# 07_CONFIG.net
KiCad netlist of a schematic drawn in Altium Designer
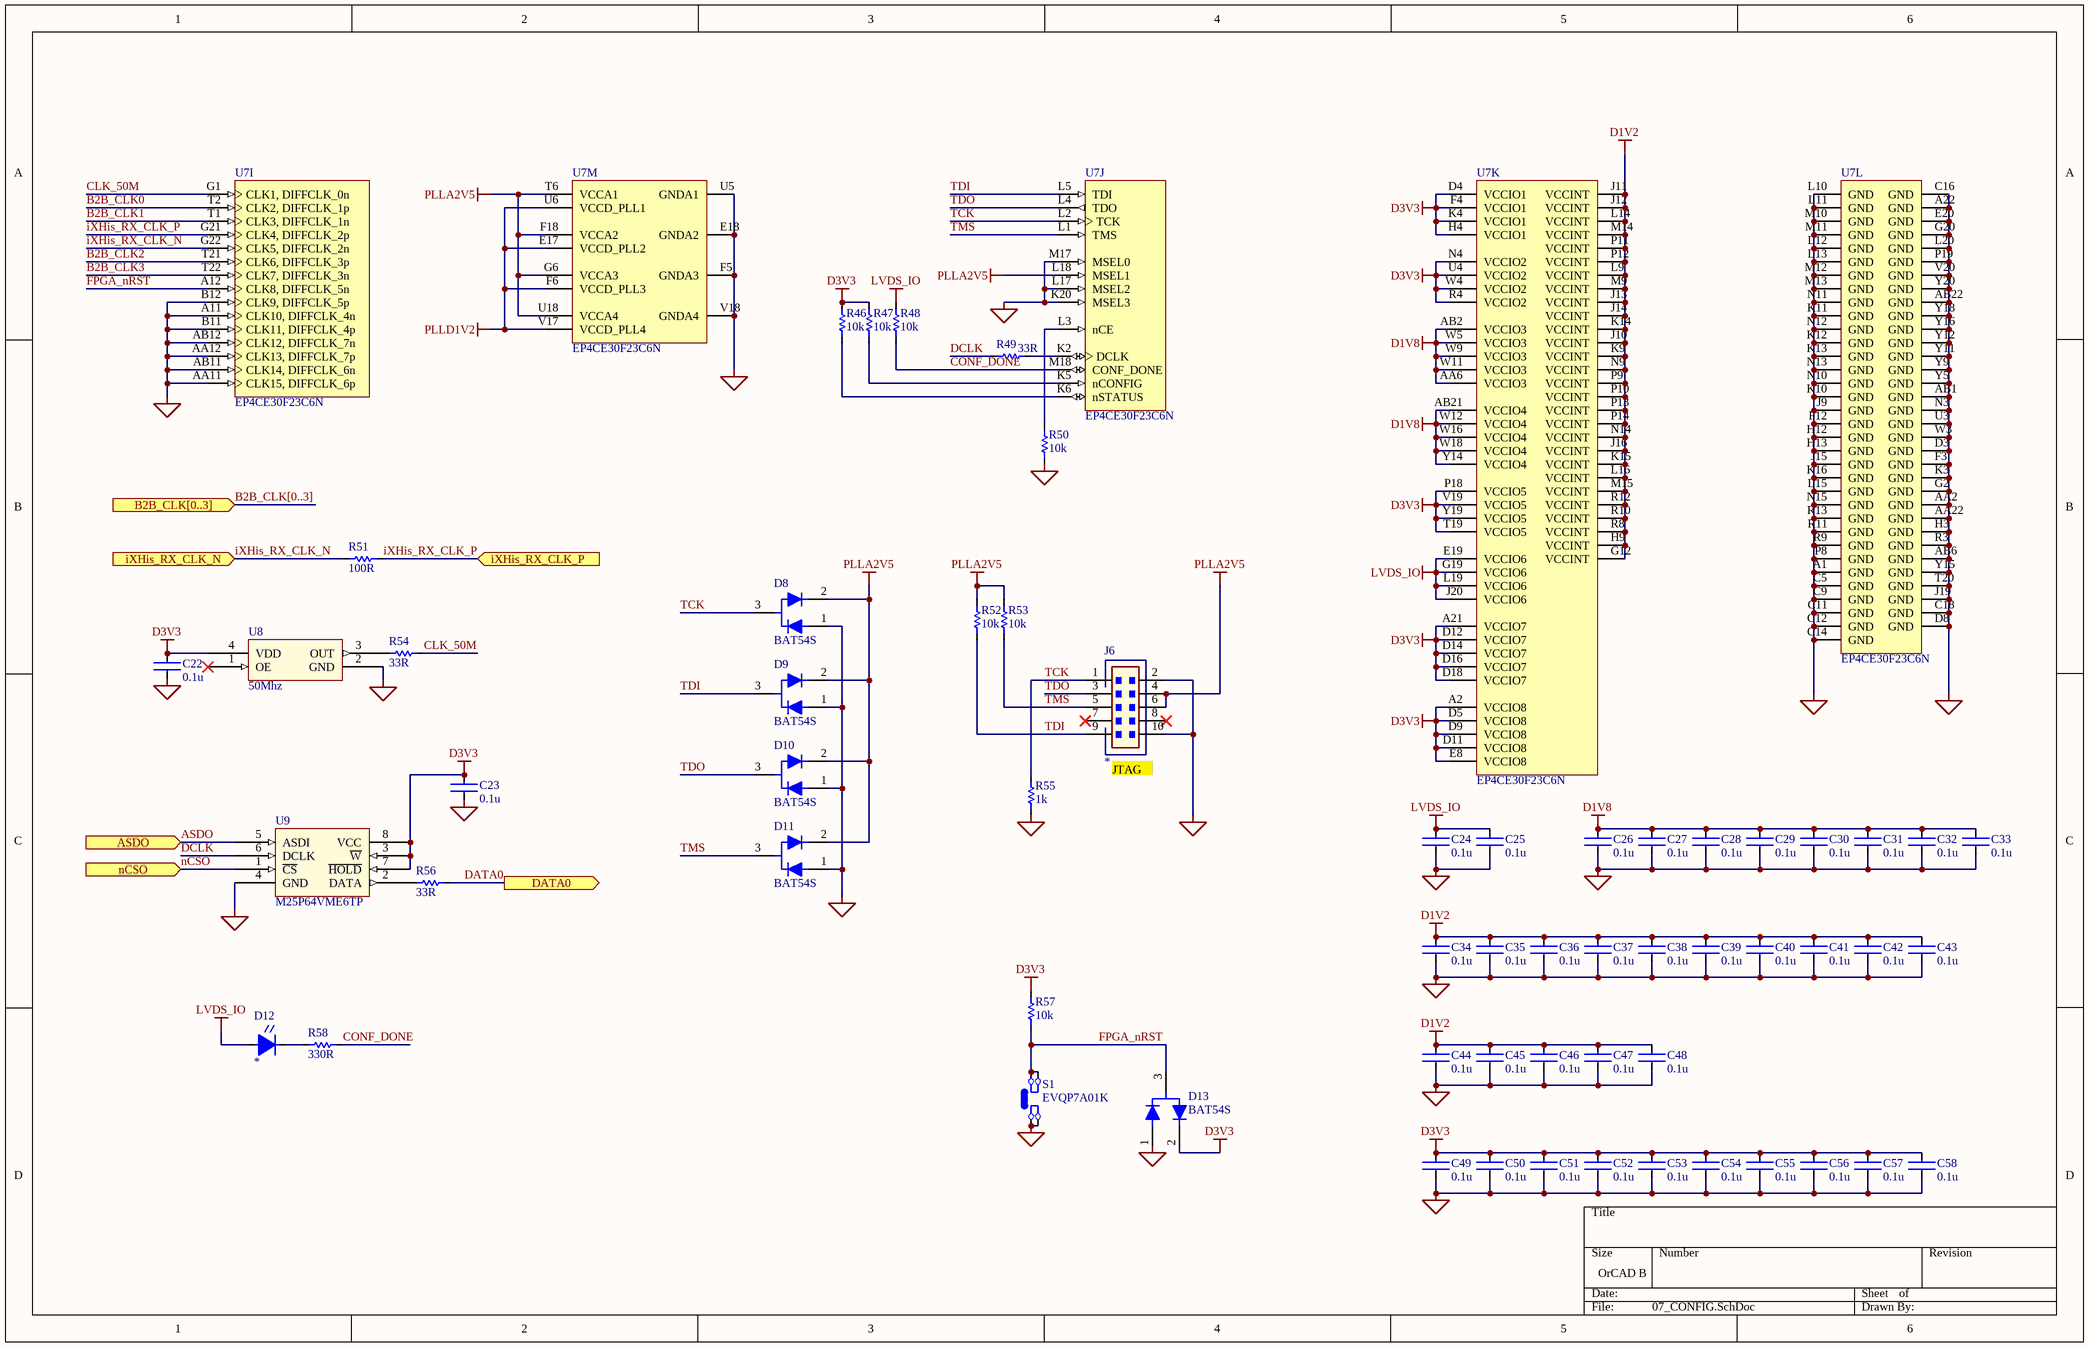
[diagram p0: 07_CONFIG.SchDoc]

(export (version "E")
  (design (tool "Eeschema 10.0.6"))
  (components
    (comp (ref "C22")
      (value "0.1u")
      (footprint "C0402")
      (description "CAP,Ceramic,X7R,10%,16V,0.1uF,0402")
      (libsource (lib "C0402") (part "CAP011"))
    )
    (comp (ref "C23")
      (value "0.1u")
      (footprint "C0402")
      (description "CAP,Ceramic,X7R,10%,16V,0.1uF,0402")
      (libsource (lib "C0402") (part "CAP011"))
    )
    (comp (ref "C24")
      (value "0.1u")
      (footprint "C0402")
      (description "CAP,Ceramic,X7R,10%,16V,0.1uF,0402")
      (libsource (lib "C0402") (part "CAP011"))
    )
    (comp (ref "C25")
      (value "0.1u")
      (footprint "C0402")
      (description "CAP,Ceramic,X7R,10%,16V,0.1uF,0402")
      (libsource (lib "C0402") (part "CAP011"))
    )
    (comp (ref "C26")
      (value "0.1u")
      (footprint "C0402")
      (description "CAP,Ceramic,X7R,10%,16V,0.1uF,0402")
      (libsource (lib "C0402") (part "CAP011"))
    )
    (comp (ref "C27")
      (value "0.1u")
      (footprint "C0402")
      (description "CAP,Ceramic,X7R,10%,16V,0.1uF,0402")
      (libsource (lib "C0402") (part "CAP011"))
    )
    (comp (ref "C28")
      (value "0.1u")
      (footprint "C0402")
      (description "CAP,Ceramic,X7R,10%,16V,0.1uF,0402")
      (libsource (lib "C0402") (part "CAP011"))
    )
    (comp (ref "C29")
      (value "0.1u")
      (footprint "C0402")
      (description "CAP,Ceramic,X7R,10%,16V,0.1uF,0402")
      (libsource (lib "C0402") (part "CAP011"))
    )
    (comp (ref "C30")
      (value "0.1u")
      (footprint "C0402")
      (description "CAP,Ceramic,X7R,10%,16V,0.1uF,0402")
      (libsource (lib "C0402") (part "CAP011"))
    )
    (comp (ref "C31")
      (value "0.1u")
      (footprint "C0402")
      (description "CAP,Ceramic,X7R,10%,16V,0.1uF,0402")
      (libsource (lib "C0402") (part "CAP011"))
    )
    (comp (ref "C32")
      (value "0.1u")
      (footprint "C0402")
      (description "CAP,Ceramic,X7R,10%,16V,0.1uF,0402")
      (libsource (lib "C0402") (part "CAP011"))
    )
    (comp (ref "C33")
      (value "0.1u")
      (footprint "C0402")
      (description "CAP,Ceramic,X7R,10%,16V,0.1uF,0402")
      (libsource (lib "C0402") (part "CAP011"))
    )
    (comp (ref "C34")
      (value "0.1u")
      (footprint "C0402")
      (description "CAP,Ceramic,X7R,10%,16V,0.1uF,0402")
      (libsource (lib "C0402") (part "CAP011"))
    )
    (comp (ref "C35")
      (value "0.1u")
      (footprint "C0402")
      (description "CAP,Ceramic,X7R,10%,16V,0.1uF,0402")
      (libsource (lib "C0402") (part "CAP011"))
    )
    (comp (ref "C36")
      (value "0.1u")
      (footprint "C0402")
      (description "CAP,Ceramic,X7R,10%,16V,0.1uF,0402")
      (libsource (lib "C0402") (part "CAP011"))
    )
    (comp (ref "C37")
      (value "0.1u")
      (footprint "C0402")
      (description "CAP,Ceramic,X7R,10%,16V,0.1uF,0402")
      (libsource (lib "C0402") (part "CAP011"))
    )
    (comp (ref "C38")
      (value "0.1u")
      (footprint "C0402")
      (description "CAP,Ceramic,X7R,10%,16V,0.1uF,0402")
      (libsource (lib "C0402") (part "CAP011"))
    )
    (comp (ref "C39")
      (value "0.1u")
      (footprint "C0402")
      (description "CAP,Ceramic,X7R,10%,16V,0.1uF,0402")
      (libsource (lib "C0402") (part "CAP011"))
    )
    (comp (ref "C40")
      (value "0.1u")
      (footprint "C0402")
      (description "CAP,Ceramic,X7R,10%,16V,0.1uF,0402")
      (libsource (lib "C0402") (part "CAP011"))
    )
    (comp (ref "C41")
      (value "0.1u")
      (footprint "C0402")
      (description "CAP,Ceramic,X7R,10%,16V,0.1uF,0402")
      (libsource (lib "C0402") (part "CAP011"))
    )
    (comp (ref "C42")
      (value "0.1u")
      (footprint "C0402")
      (description "CAP,Ceramic,X7R,10%,16V,0.1uF,0402")
      (libsource (lib "C0402") (part "CAP011"))
    )
    (comp (ref "C43")
      (value "0.1u")
      (footprint "C0402")
      (description "CAP,Ceramic,X7R,10%,16V,0.1uF,0402")
      (libsource (lib "C0402") (part "CAP011"))
    )
    (comp (ref "C44")
      (value "0.1u")
      (footprint "C0402")
      (description "CAP,Ceramic,X7R,10%,16V,0.1uF,0402")
      (libsource (lib "C0402") (part "CAP011"))
    )
    (comp (ref "C45")
      (value "0.1u")
      (footprint "C0402")
      (description "CAP,Ceramic,X7R,10%,16V,0.1uF,0402")
      (libsource (lib "C0402") (part "CAP011"))
    )
    (comp (ref "C46")
      (value "0.1u")
      (footprint "C0402")
      (description "CAP,Ceramic,X7R,10%,16V,0.1uF,0402")
      (libsource (lib "C0402") (part "CAP011"))
    )
    (comp (ref "C47")
      (value "0.1u")
      (footprint "C0402")
      (description "CAP,Ceramic,X7R,10%,16V,0.1uF,0402")
      (libsource (lib "C0402") (part "CAP011"))
    )
    (comp (ref "C48")
      (value "0.1u")
      (footprint "C0402")
      (description "CAP,Ceramic,X7R,10%,16V,0.1uF,0402")
      (libsource (lib "C0402") (part "CAP011"))
    )
    (comp (ref "C49")
      (value "0.1u")
      (footprint "C0402")
      (description "CAP,Ceramic,X7R,10%,16V,0.1uF,0402")
      (libsource (lib "C0402") (part "CAP011"))
    )
    (comp (ref "C50")
      (value "0.1u")
      (footprint "C0402")
      (description "CAP,Ceramic,X7R,10%,16V,0.1uF,0402")
      (libsource (lib "C0402") (part "CAP011"))
    )
    (comp (ref "C51")
      (value "0.1u")
      (footprint "C0402")
      (description "CAP,Ceramic,X7R,10%,16V,0.1uF,0402")
      (libsource (lib "C0402") (part "CAP011"))
    )
    (comp (ref "C52")
      (value "0.1u")
      (footprint "C0402")
      (description "CAP,Ceramic,X7R,10%,16V,0.1uF,0402")
      (libsource (lib "C0402") (part "CAP011"))
    )
    (comp (ref "C53")
      (value "0.1u")
      (footprint "C0402")
      (description "CAP,Ceramic,X7R,10%,16V,0.1uF,0402")
      (libsource (lib "C0402") (part "CAP011"))
    )
    (comp (ref "C54")
      (value "0.1u")
      (footprint "C0402")
      (description "CAP,Ceramic,X7R,10%,16V,0.1uF,0402")
      (libsource (lib "C0402") (part "CAP011"))
    )
    (comp (ref "C55")
      (value "0.1u")
      (footprint "C0402")
      (description "CAP,Ceramic,X7R,10%,16V,0.1uF,0402")
      (libsource (lib "C0402") (part "CAP011"))
    )
    (comp (ref "C56")
      (value "0.1u")
      (footprint "C0402")
      (description "CAP,Ceramic,X7R,10%,16V,0.1uF,0402")
      (libsource (lib "C0402") (part "CAP011"))
    )
    (comp (ref "C57")
      (value "0.1u")
      (footprint "C0402")
      (description "CAP,Ceramic,X7R,10%,16V,0.1uF,0402")
      (libsource (lib "C0402") (part "CAP011"))
    )
    (comp (ref "C58")
      (value "0.1u")
      (footprint "C0402")
      (description "CAP,Ceramic,X7R,10%,16V,0.1uF,0402")
      (libsource (lib "C0402") (part "CAP011"))
    )
    (comp (ref "D8")
      (value "BAT54S")
      (footprint "SOT95P230X110-3N_SOT23_BAT54")
      (description "Schottky Double Diodes,30V,200mA,SOT23,a1k2k1a2")
      (libsource (lib "AD15_schlib") (part "BAT54S"))
    )
    (comp (ref "D9")
      (value "BAT54S")
      (footprint "SOT95P230X110-3N_SOT23_BAT54")
      (description "Schottky Double Diodes,30V,200mA,SOT23,a1k2k1a2")
      (libsource (lib "AD15_schlib") (part "BAT54S"))
    )
    (comp (ref "D10")
      (value "BAT54S")
      (footprint "SOT95P230X110-3N_SOT23_BAT54")
      (description "Schottky Double Diodes,30V,200mA,SOT23,a1k2k1a2")
      (libsource (lib "AD15_schlib") (part "BAT54S"))
    )
    (comp (ref "D11")
      (value "BAT54S")
      (footprint "SOT95P230X110-3N_SOT23_BAT54")
      (description "Schottky Double Diodes,30V,200mA,SOT23,a1k2k1a2")
      (libsource (lib "AD15_schlib") (part "BAT54S"))
    )
    (comp (ref "D12")
      (value "*")
      (footprint "LED0603")
      (description "LED,Yellow Green,2V,20mA,0603")
      (libsource (lib "AD15_schlib") (part "LED YellowGreen0603"))
    )
    (comp (ref "D13")
      (value "BAT54S")
      (footprint "SOT95P230X110-3N_SOT23_BAT54")
      (description "Schottky Double Diodes,30V,200mA,SOT23,a1k2k1a2")
      (libsource (lib "AD15_schlib") (part "BAT54S"))
    )
    (comp (ref "J6")
      (value "JTAG")
      (footprint "3011001XXX00")
      (description "Header,10Pin,Vertical,2.54mm Pitch,TH")
      (fields (field (name "COMMENT_1") "*"))
      (libsource (lib "AD15_schlib") (part "3011001XXX00"))
    )
    (comp (ref "R46")
      (value "10k")
      (footprint "R0402")
      (description "RES,10k,1%,1/16W,0402")
      (libsource (lib "R0402") (part "RES012"))
    )
    (comp (ref "R47")
      (value "10k")
      (footprint "R0402")
      (description "RES,10k,1%,1/16W,0402")
      (libsource (lib "R0402") (part "RES012"))
    )
    (comp (ref "R48")
      (value "10k")
      (footprint "R0402")
      (description "RES,10k,1%,1/16W,0402")
      (libsource (lib "R0402") (part "RES012"))
    )
    (comp (ref "R49")
      (value "33R")
      (footprint "R0402")
      (description "RES,33R,1%,1/16W,0402")
      (libsource (lib "R0402") (part "RES017"))
    )
    (comp (ref "R50")
      (value "10k")
      (footprint "R0402")
      (description "RES,10k,1%,1/16W,0402")
      (libsource (lib "R0402") (part "RES012"))
    )
    (comp (ref "R51")
      (value "100R")
      (footprint "R0402")
      (description "RES,100R,1%,1/16W,0402")
      (libsource (lib "R0402") (part "RES019"))
    )
    (comp (ref "R52")
      (value "10k")
      (footprint "R0402")
      (description "RES,10k,1%,1/16W,0402")
      (libsource (lib "R0402") (part "RES012"))
    )
    (comp (ref "R53")
      (value "10k")
      (footprint "R0402")
      (description "RES,10k,1%,1/16W,0402")
      (libsource (lib "R0402") (part "RES012"))
    )
    (comp (ref "R54")
      (value "33R")
      (footprint "R0402")
      (description "RES,33R,1%,1/16W,0402")
      (libsource (lib "R0402") (part "RES017"))
    )
    (comp (ref "R55")
      (value "1k")
      (footprint "R0402")
      (description "RES,1k,1%,1/16W,0402")
      (libsource (lib "R0402") (part "RES011"))
    )
    (comp (ref "R56")
      (value "33R")
      (footprint "R0402")
      (description "RES,33R,1%,1/16W,0402")
      (libsource (lib "R0402") (part "RES017"))
    )
    (comp (ref "R57")
      (value "10k")
      (footprint "R0402")
      (description "RES,10k,1%,1/16W,0402")
      (libsource (lib "R0402") (part "RES012"))
    )
    (comp (ref "R58")
      (value "330R")
      (footprint "R0402")
      (description "RES,330R,1%,1/16W,0402")
      (libsource (lib "R0402") (part "RES0111"))
    )
    (comp (ref "S1")
      (value "EVQP7A01K")
      (footprint "EVQP7A01K")
      (description "Switch,3.5x2.9,Normal open,SMD")
      (libsource (lib "AD15_schlib") (part "EVQP7A01K"))
    )
    (comp (ref "U7")
      (value "EP4CE30F23C6N")
      (footprint "FBGA484_EP4CE30F23C6N")
      (description "IC,FPGA,28848 LEs,Speed-6,FBGA484")
      (libsource (lib "AD15_Altera_schlib") (part "EP4CE30F23C6N"))
    )
    (comp (ref "U8")
      (value "50Mhz")
      (footprint "3225_DSO321SR")
      (description "IC,OSC,50MHz,3.3V,100ppm,3225")
      (libsource (lib "AD15_schlib") (part "DSO321SRAA-50MHz"))
    )
    (comp (ref "U9")
      (value "M25P64VME6TP")
      (footprint "VDFPN8_M25P64")
      (description "IC,FLASH,64 Mbit,SPI,VDFPN8")
      (libsource (lib "Micron") (part "M25P64VME6TP"))
    )
  )
  (nets
    (net (code "1") (name "/ASDO") (class "Default")
      (node (ref "U9") (pin "5") (pinfunction "ASDI_5") (pintype "input"))
    )
    (net (code "2") (name "/B2B_CLK0") (class "Default")
      (node (ref "U7") (pin "T2") (pinfunction "CLK2,_DIFFCLK_1p_T2") (pintype "input"))
    )
    (net (code "3") (name "/B2B_CLK1") (class "Default")
      (node (ref "U7") (pin "T1") (pinfunction "CLK3,_DIFFCLK_1n_T1") (pintype "input"))
    )
    (net (code "4") (name "/B2B_CLK2") (class "Default")
      (node (ref "U7") (pin "T21") (pinfunction "CLK6,_DIFFCLK_3p_T21") (pintype "input"))
    )
    (net (code "5") (name "/B2B_CLK3") (class "Default")
      (node (ref "U7") (pin "T22") (pinfunction "CLK7,_DIFFCLK_3n_T22") (pintype "input"))
    )
    (net (code "7") (name "/CLK_50M") (class "Default")
      (node (ref "R54") (pin "2") (pinfunction "2_2") (pintype "passive"))
      (node (ref "U7") (pin "G1") (pinfunction "CLK1,_DIFFCLK_0n_G1") (pintype "input"))
    )
    (net (code "8") (name "/CONF_DONE") (class "Default")
      (node (ref "R48") (pin "1") (pinfunction "0_1") (pintype "passive"))
      (node (ref "R58") (pin "2") (pinfunction "2_2") (pintype "passive"))
      (node (ref "U7") (pin "M18") (pinfunction "CONF_DONE_M18") (pintype "bidirectional"))
    )
    (net (code "9") (name "/DATA0") (class "Default")
      (node (ref "R56") (pin "2") (pinfunction "2_2") (pintype "passive"))
    )
    (net (code "10") (name "/DCLK") (class "Default")
      (node (ref "R49") (pin "1") (pinfunction "0_1") (pintype "passive"))
      (node (ref "U9") (pin "6") (pinfunction "DCLK_6") (pintype "input"))
    )
    (net (code "11") (name "/FPGA_nRST") (class "Default")
      (node (ref "D13") (pin "3") (pinfunction "2_3") (pintype "passive"))
      (node (ref "R57") (pin "1") (pinfunction "0_1") (pintype "passive"))
      (node (ref "S1") (pin "2") (pinfunction "CVdd_2") (pintype "passive"))
      (node (ref "U7") (pin "A12") (pinfunction "CLK8,_DIFFCLK_5n_A12") (pintype "input"))
    )
    (net (code "12") (name "/TCK") (class "Default")
      (node (ref "D8") (pin "3") (pinfunction "2_3") (pintype "passive"))
      (node (ref "J6") (pin "1") (pinfunction "0_1") (pintype "passive"))
      (node (ref "R55") (pin "2") (pinfunction "2_2") (pintype "passive"))
      (node (ref "U7") (pin "L2") (pinfunction "TCK_L2") (pintype "input"))
    )
    (net (code "13") (name "/TDI") (class "Default")
      (node (ref "D9") (pin "3") (pinfunction "2_3") (pintype "passive"))
      (node (ref "J6") (pin "9") (pinfunction "9_9") (pintype "passive"))
      (node (ref "R52") (pin "1") (pinfunction "0_1") (pintype "passive"))
      (node (ref "U7") (pin "L5") (pinfunction "TDI_L5") (pintype "input"))
    )
    (net (code "14") (name "/TDO") (class "Default")
      (node (ref "D10") (pin "3") (pinfunction "2_3") (pintype "passive"))
      (node (ref "J6") (pin "3") (pinfunction "2_3") (pintype "passive"))
      (node (ref "U7") (pin "L4") (pinfunction "TDO_L4") (pintype "output"))
    )
    (net (code "15") (name "/TMS") (class "Default")
      (node (ref "D11") (pin "3") (pinfunction "2_3") (pintype "passive"))
      (node (ref "J6") (pin "5") (pinfunction "4_5") (pintype "passive"))
      (node (ref "R53") (pin "1") (pinfunction "0_1") (pintype "passive"))
      (node (ref "U7") (pin "L1") (pinfunction "TMS_L1") (pintype "input"))
    )
    (net (code "16") (name "/iXHis_RX_CLK_N") (class "Default")
      (node (ref "R51") (pin "1") (pinfunction "0_1") (pintype "passive"))
      (node (ref "U7") (pin "G22") (pinfunction "CLK5,_DIFFCLK_2n_G22") (pintype "input"))
    )
    (net (code "17") (name "/iXHis_RX_CLK_P") (class "Default")
      (node (ref "R51") (pin "2") (pinfunction "2_2") (pintype "passive"))
      (node (ref "U7") (pin "G21") (pinfunction "CLK4,_DIFFCLK_2p_G21") (pintype "input"))
    )
    (net (code "18") (name "/nCSO") (class "Default")
      (node (ref "U9") (pin "1") (pinfunction "~{CS}_1") (pintype "input"))
    )
    (net (code "19") (name "D1V2") (class "Default")
      (node (ref "C34") (pin "1") (pinfunction "0_1") (pintype "passive"))
      (node (ref "C35") (pin "1") (pinfunction "0_1") (pintype "passive"))
      (node (ref "C36") (pin "1") (pinfunction "0_1") (pintype "passive"))
      (node (ref "C37") (pin "1") (pinfunction "0_1") (pintype "passive"))
      (node (ref "C38") (pin "1") (pinfunction "0_1") (pintype "passive"))
      (node (ref "C39") (pin "1") (pinfunction "0_1") (pintype "passive"))
      (node (ref "C40") (pin "1") (pinfunction "0_1") (pintype "passive"))
      (node (ref "C41") (pin "1") (pinfunction "0_1") (pintype "passive"))
      (node (ref "C42") (pin "1") (pinfunction "0_1") (pintype "passive"))
      (node (ref "C43") (pin "1") (pinfunction "0_1") (pintype "passive"))
      (node (ref "C44") (pin "1") (pinfunction "0_1") (pintype "passive"))
      (node (ref "C45") (pin "1") (pinfunction "0_1") (pintype "passive"))
      (node (ref "C46") (pin "1") (pinfunction "0_1") (pintype "passive"))
      (node (ref "C47") (pin "1") (pinfunction "0_1") (pintype "passive"))
      (node (ref "C48") (pin "1") (pinfunction "0_1") (pintype "passive"))
      (node (ref "U7") (pin "G12") (pinfunction "VCCINT_G12") (pintype "power_in"))
      (node (ref "U7") (pin "H9") (pinfunction "VCCINT_H9") (pintype "power_in"))
      (node (ref "U7") (pin "J10") (pinfunction "VCCINT_J10") (pintype "power_in"))
      (node (ref "U7") (pin "J11") (pinfunction "VCCINT_J11") (pintype "power_in"))
      (node (ref "U7") (pin "J12") (pinfunction "VCCINT_J12") (pintype "power_in"))
      (node (ref "U7") (pin "J13") (pinfunction "VCCINT_J13") (pintype "power_in"))
      (node (ref "U7") (pin "J14") (pinfunction "VCCINT_J14") (pintype "power_in"))
      (node (ref "U7") (pin "J16") (pinfunction "VCCINT_J16") (pintype "power_in"))
      (node (ref "U7") (pin "K14") (pinfunction "VCCINT_K14") (pintype "power_in"))
      (node (ref "U7") (pin "K15") (pinfunction "VCCINT_K15") (pintype "power_in"))
      (node (ref "U7") (pin "K9") (pinfunction "VCCINT_K9") (pintype "power_in"))
      (node (ref "U7") (pin "L14") (pinfunction "VCCINT_L14") (pintype "power_in"))
      (node (ref "U7") (pin "L16") (pinfunction "VCCINT_L16") (pintype "power_in"))
      (node (ref "U7") (pin "L9") (pinfunction "VCCINT_L9") (pintype "power_in"))
      (node (ref "U7") (pin "M14") (pinfunction "VCCINT_M14") (pintype "power_in"))
      (node (ref "U7") (pin "M15") (pinfunction "VCCINT_M15") (pintype "power_in"))
      (node (ref "U7") (pin "M9") (pinfunction "VCCINT_M9") (pintype "power_in"))
      (node (ref "U7") (pin "N14") (pinfunction "VCCINT_N14") (pintype "power_in"))
      (node (ref "U7") (pin "N9") (pinfunction "VCCINT_N9") (pintype "power_in"))
      (node (ref "U7") (pin "P10") (pinfunction "VCCINT_P10") (pintype "power_in"))
      (node (ref "U7") (pin "P11") (pinfunction "VCCINT_P11") (pintype "power_in"))
      (node (ref "U7") (pin "P12") (pinfunction "VCCINT_P12") (pintype "power_in"))
      (node (ref "U7") (pin "P13") (pinfunction "VCCINT_P13") (pintype "power_in"))
      (node (ref "U7") (pin "P14") (pinfunction "VCCINT_P14") (pintype "power_in"))
      (node (ref "U7") (pin "P9") (pinfunction "VCCINT_P9") (pintype "power_in"))
      (node (ref "U7") (pin "R10") (pinfunction "VCCINT_R10") (pintype "power_in"))
      (node (ref "U7") (pin "R12") (pinfunction "VCCINT_R12") (pintype "power_in"))
      (node (ref "U7") (pin "R8") (pinfunction "VCCINT_R8") (pintype "power_in"))
    )
    (net (code "20") (name "D1V8") (class "Default")
      (node (ref "C26") (pin "1") (pinfunction "0_1") (pintype "passive"))
      (node (ref "C27") (pin "1") (pinfunction "0_1") (pintype "passive"))
      (node (ref "C28") (pin "1") (pinfunction "0_1") (pintype "passive"))
      (node (ref "C29") (pin "1") (pinfunction "0_1") (pintype "passive"))
      (node (ref "C30") (pin "1") (pinfunction "0_1") (pintype "passive"))
      (node (ref "C31") (pin "1") (pinfunction "0_1") (pintype "passive"))
      (node (ref "C32") (pin "1") (pinfunction "0_1") (pintype "passive"))
      (node (ref "C33") (pin "1") (pinfunction "0_1") (pintype "passive"))
      (node (ref "U7") (pin "AA6") (pinfunction "VCCIO3_AA6") (pintype "power_in"))
      (node (ref "U7") (pin "AB2") (pinfunction "VCCIO3_AB2") (pintype "power_in"))
      (node (ref "U7") (pin "AB21") (pinfunction "VCCIO4_AB21") (pintype "power_in"))
      (node (ref "U7") (pin "W11") (pinfunction "VCCIO3_W11") (pintype "power_in"))
      (node (ref "U7") (pin "W12") (pinfunction "VCCIO4_W12") (pintype "power_in"))
      (node (ref "U7") (pin "W16") (pinfunction "VCCIO4_W16") (pintype "power_in"))
      (node (ref "U7") (pin "W18") (pinfunction "VCCIO4_W18") (pintype "power_in"))
      (node (ref "U7") (pin "W5") (pinfunction "VCCIO3_W5") (pintype "power_in"))
      (node (ref "U7") (pin "W9") (pinfunction "VCCIO3_W9") (pintype "power_in"))
      (node (ref "U7") (pin "Y14") (pinfunction "VCCIO4_Y14") (pintype "power_in"))
    )
    (net (code "21") (name "D3V3") (class "Default")
      (node (ref "C22") (pin "1") (pinfunction "0_1") (pintype "passive"))
      (node (ref "C23") (pin "1") (pinfunction "0_1") (pintype "passive"))
      (node (ref "C49") (pin "1") (pinfunction "0_1") (pintype "passive"))
      (node (ref "C50") (pin "1") (pinfunction "0_1") (pintype "passive"))
      (node (ref "C51") (pin "1") (pinfunction "0_1") (pintype "passive"))
      (node (ref "C52") (pin "1") (pinfunction "0_1") (pintype "passive"))
      (node (ref "C53") (pin "1") (pinfunction "0_1") (pintype "passive"))
      (node (ref "C54") (pin "1") (pinfunction "0_1") (pintype "passive"))
      (node (ref "C55") (pin "1") (pinfunction "0_1") (pintype "passive"))
      (node (ref "C56") (pin "1") (pinfunction "0_1") (pintype "passive"))
      (node (ref "C57") (pin "1") (pinfunction "0_1") (pintype "passive"))
      (node (ref "C58") (pin "1") (pinfunction "0_1") (pintype "passive"))
      (node (ref "D13") (pin "2") (pinfunction "1_2") (pintype "passive"))
      (node (ref "R46") (pin "2") (pinfunction "2_2") (pintype "passive"))
      (node (ref "R47") (pin "2") (pinfunction "2_2") (pintype "passive"))
      (node (ref "R57") (pin "2") (pinfunction "2_2") (pintype "passive"))
      (node (ref "U7") (pin "A2") (pinfunction "VCCIO8_A2") (pintype "power_in"))
      (node (ref "U7") (pin "A21") (pinfunction "VCCIO7_A21") (pintype "power_in"))
      (node (ref "U7") (pin "D11") (pinfunction "VCCIO8_D11") (pintype "power_in"))
      (node (ref "U7") (pin "D12") (pinfunction "VCCIO7_D12") (pintype "power_in"))
      (node (ref "U7") (pin "D14") (pinfunction "VCCIO7_D14") (pintype "power_in"))
      (node (ref "U7") (pin "D16") (pinfunction "VCCIO7_D16") (pintype "power_in"))
      (node (ref "U7") (pin "D18") (pinfunction "VCCIO7_D18") (pintype "power_in"))
      (node (ref "U7") (pin "D4") (pinfunction "VCCIO1_D4") (pintype "power_in"))
      (node (ref "U7") (pin "D5") (pinfunction "VCCIO8_D5") (pintype "power_in"))
      (node (ref "U7") (pin "D9") (pinfunction "VCCIO8_D9") (pintype "power_in"))
      (node (ref "U7") (pin "E8") (pinfunction "VCCIO8_E8") (pintype "power_in"))
      (node (ref "U7") (pin "F4") (pinfunction "VCCIO1_F4") (pintype "power_in"))
      (node (ref "U7") (pin "H4") (pinfunction "VCCIO1_H4") (pintype "power_in"))
      (node (ref "U7") (pin "K4") (pinfunction "VCCIO1_K4") (pintype "power_in"))
      (node (ref "U7") (pin "N4") (pinfunction "VCCIO2_N4") (pintype "power_in"))
      (node (ref "U7") (pin "P18") (pinfunction "VCCIO5_P18") (pintype "power_in"))
      (node (ref "U7") (pin "R4") (pinfunction "VCCIO2_R4") (pintype "power_in"))
      (node (ref "U7") (pin "T19") (pinfunction "VCCIO5_T19") (pintype "power_in"))
      (node (ref "U7") (pin "U4") (pinfunction "VCCIO2_U4") (pintype "power_in"))
      (node (ref "U7") (pin "V19") (pinfunction "VCCIO5_V19") (pintype "power_in"))
      (node (ref "U7") (pin "W4") (pinfunction "VCCIO2_W4") (pintype "power_in"))
      (node (ref "U7") (pin "Y19") (pinfunction "VCCIO5_Y19") (pintype "power_in"))
      (node (ref "U8") (pin "4") (pinfunction "VDD_4") (pintype "power_in"))
      (node (ref "U9") (pin "3") (pinfunction "~{W}_3") (pintype "input"))
      (node (ref "U9") (pin "7") (pinfunction "~{HOLD}_7") (pintype "input"))
      (node (ref "U9") (pin "8") (pinfunction "VCC_8") (pintype "power_in"))
    )
    (net (code "22") (name "GND") (class "Default")
      (node (ref "C22") (pin "2") (pinfunction "1_2") (pintype "passive"))
      (node (ref "C23") (pin "2") (pinfunction "1_2") (pintype "passive"))
      (node (ref "C24") (pin "2") (pinfunction "1_2") (pintype "passive"))
      (node (ref "C25") (pin "2") (pinfunction "1_2") (pintype "passive"))
      (node (ref "C26") (pin "2") (pinfunction "1_2") (pintype "passive"))
      (node (ref "C27") (pin "2") (pinfunction "1_2") (pintype "passive"))
      (node (ref "C28") (pin "2") (pinfunction "1_2") (pintype "passive"))
      (node (ref "C29") (pin "2") (pinfunction "1_2") (pintype "passive"))
      (node (ref "C30") (pin "2") (pinfunction "1_2") (pintype "passive"))
      (node (ref "C31") (pin "2") (pinfunction "1_2") (pintype "passive"))
      (node (ref "C32") (pin "2") (pinfunction "1_2") (pintype "passive"))
      (node (ref "C33") (pin "2") (pinfunction "1_2") (pintype "passive"))
      (node (ref "C34") (pin "2") (pinfunction "1_2") (pintype "passive"))
      (node (ref "C35") (pin "2") (pinfunction "1_2") (pintype "passive"))
      (node (ref "C36") (pin "2") (pinfunction "1_2") (pintype "passive"))
      (node (ref "C37") (pin "2") (pinfunction "1_2") (pintype "passive"))
      (node (ref "C38") (pin "2") (pinfunction "1_2") (pintype "passive"))
      (node (ref "C39") (pin "2") (pinfunction "1_2") (pintype "passive"))
      (node (ref "C40") (pin "2") (pinfunction "1_2") (pintype "passive"))
      (node (ref "C41") (pin "2") (pinfunction "1_2") (pintype "passive"))
      (node (ref "C42") (pin "2") (pinfunction "1_2") (pintype "passive"))
      (node (ref "C43") (pin "2") (pinfunction "1_2") (pintype "passive"))
      (node (ref "C44") (pin "2") (pinfunction "1_2") (pintype "passive"))
      (node (ref "C45") (pin "2") (pinfunction "1_2") (pintype "passive"))
      (node (ref "C46") (pin "2") (pinfunction "1_2") (pintype "passive"))
      (node (ref "C47") (pin "2") (pinfunction "1_2") (pintype "passive"))
      (node (ref "C48") (pin "2") (pinfunction "1_2") (pintype "passive"))
      (node (ref "C49") (pin "2") (pinfunction "1_2") (pintype "passive"))
      (node (ref "C50") (pin "2") (pinfunction "1_2") (pintype "passive"))
      (node (ref "C51") (pin "2") (pinfunction "1_2") (pintype "passive"))
      (node (ref "C52") (pin "2") (pinfunction "1_2") (pintype "passive"))
      (node (ref "C53") (pin "2") (pinfunction "1_2") (pintype "passive"))
      (node (ref "C54") (pin "2") (pinfunction "1_2") (pintype "passive"))
      (node (ref "C55") (pin "2") (pinfunction "1_2") (pintype "passive"))
      (node (ref "C56") (pin "2") (pinfunction "1_2") (pintype "passive"))
      (node (ref "C57") (pin "2") (pinfunction "1_2") (pintype "passive"))
      (node (ref "C58") (pin "2") (pinfunction "1_2") (pintype "passive"))
      (node (ref "D10") (pin "1") (pinfunction "0_1") (pintype "passive"))
      (node (ref "D11") (pin "1") (pinfunction "0_1") (pintype "passive"))
      (node (ref "D13") (pin "1") (pinfunction "0_1") (pintype "passive"))
      (node (ref "D8") (pin "1") (pinfunction "0_1") (pintype "passive"))
      (node (ref "D9") (pin "1") (pinfunction "0_1") (pintype "passive"))
      (node (ref "J6") (pin "10") (pinfunction "9_10") (pintype "passive"))
      (node (ref "J6") (pin "2") (pinfunction "1_2") (pintype "passive"))
      (node (ref "R50") (pin "1") (pinfunction "0_1") (pintype "passive"))
      (node (ref "R55") (pin "1") (pinfunction "0_1") (pintype "passive"))
      (node (ref "S1") (pin "1") (pinfunction "CVdd_1") (pintype "passive"))
      (node (ref "U7") (pin "A1") (pinfunction "GND_A1") (pintype "power_in"))
      (node (ref "U7") (pin "A11") (pinfunction "CLK10,_DIFFCLK_4n_A11") (pintype "input"))
      (node (ref "U7") (pin "A22") (pinfunction "GND_A22") (pintype "power_in"))
      (node (ref "U7") (pin "AA11") (pinfunction "CLK15,_DIFFCLK_6p_AA11") (pintype "input"))
      (node (ref "U7") (pin "AA12") (pinfunction "CLK13,_DIFFCLK_7p_AA12") (pintype "input"))
      (node (ref "U7") (pin "AA2") (pinfunction "GND_AA2") (pintype "power_in"))
      (node (ref "U7") (pin "AA22") (pinfunction "GND_AA22") (pintype "power_in"))
      (node (ref "U7") (pin "AB1") (pinfunction "GND_AB1") (pintype "power_in"))
      (node (ref "U7") (pin "AB11") (pinfunction "CLK14,_DIFFCLK_6n_AB11") (pintype "input"))
      (node (ref "U7") (pin "AB12") (pinfunction "CLK12,_DIFFCLK_7n_AB12") (pintype "input"))
      (node (ref "U7") (pin "AB22") (pinfunction "GND_AB22") (pintype "power_in"))
      (node (ref "U7") (pin "AB6") (pinfunction "GND_AB6") (pintype "power_in"))
      (node (ref "U7") (pin "B11") (pinfunction "CLK11,_DIFFCLK_4p_B11") (pintype "input"))
      (node (ref "U7") (pin "B12") (pinfunction "CLK9,_DIFFCLK_5p_B12") (pintype "input"))
      (node (ref "U7") (pin "C11") (pinfunction "GND_C11") (pintype "power_in"))
      (node (ref "U7") (pin "C12") (pinfunction "GND_C12") (pintype "power_in"))
      (node (ref "U7") (pin "C14") (pinfunction "GND_C14") (pintype "power_in"))
      (node (ref "U7") (pin "C16") (pinfunction "GND_C16") (pintype "power_in"))
      (node (ref "U7") (pin "C18") (pinfunction "GND_C18") (pintype "power_in"))
      (node (ref "U7") (pin "C5") (pinfunction "GND_C5") (pintype "power_in"))
      (node (ref "U7") (pin "C9") (pinfunction "GND_C9") (pintype "power_in"))
      (node (ref "U7") (pin "D3") (pinfunction "GND_D3") (pintype "power_in"))
      (node (ref "U7") (pin "D8") (pinfunction "GND_D8") (pintype "power_in"))
      (node (ref "U7") (pin "E18") (pinfunction "GNDA2_E18") (pintype "power_in"))
      (node (ref "U7") (pin "E20") (pinfunction "GND_E20") (pintype "power_in"))
      (node (ref "U7") (pin "F12") (pinfunction "GND_F12") (pintype "power_in"))
      (node (ref "U7") (pin "F3") (pinfunction "GND_F3") (pintype "power_in"))
      (node (ref "U7") (pin "F5") (pinfunction "GNDA3_F5") (pintype "power_in"))
      (node (ref "U7") (pin "G2") (pinfunction "GND_G2") (pintype "power_in"))
      (node (ref "U7") (pin "G20") (pinfunction "GND_G20") (pintype "power_in"))
      (node (ref "U7") (pin "H12") (pinfunction "GND_H12") (pintype "power_in"))
      (node (ref "U7") (pin "H13") (pinfunction "GND_H13") (pintype "power_in"))
      (node (ref "U7") (pin "H3") (pinfunction "GND_H3") (pintype "power_in"))
      (node (ref "U7") (pin "J15") (pinfunction "GND_J15") (pintype "power_in"))
      (node (ref "U7") (pin "J19") (pinfunction "GND_J19") (pintype "power_in"))
      (node (ref "U7") (pin "J9") (pinfunction "GND_J9") (pintype "power_in"))
      (node (ref "U7") (pin "K10") (pinfunction "GND_K10") (pintype "power_in"))
      (node (ref "U7") (pin "K11") (pinfunction "GND_K11") (pintype "power_in"))
      (node (ref "U7") (pin "K12") (pinfunction "GND_K12") (pintype "power_in"))
      (node (ref "U7") (pin "K13") (pinfunction "GND_K13") (pintype "power_in"))
      (node (ref "U7") (pin "K16") (pinfunction "GND_K16") (pintype "power_in"))
      (node (ref "U7") (pin "K20") (pinfunction "MSEL3_K20") (pintype "input"))
      (node (ref "U7") (pin "K3") (pinfunction "GND_K3") (pintype "power_in"))
      (node (ref "U7") (pin "L10") (pinfunction "GND_L10") (pintype "power_in"))
      (node (ref "U7") (pin "L11") (pinfunction "GND_L11") (pintype "power_in"))
      (node (ref "U7") (pin "L12") (pinfunction "GND_L12") (pintype "power_in"))
      (node (ref "U7") (pin "L13") (pinfunction "GND_L13") (pintype "power_in"))
      (node (ref "U7") (pin "L15") (pinfunction "GND_L15") (pintype "power_in"))
      (node (ref "U7") (pin "L17") (pinfunction "MSEL2_L17") (pintype "input"))
      (node (ref "U7") (pin "L20") (pinfunction "GND_L20") (pintype "power_in"))
      (node (ref "U7") (pin "M10") (pinfunction "GND_M10") (pintype "power_in"))
      (node (ref "U7") (pin "M11") (pinfunction "GND_M11") (pintype "power_in"))
      (node (ref "U7") (pin "M12") (pinfunction "GND_M12") (pintype "power_in"))
      (node (ref "U7") (pin "M13") (pinfunction "GND_M13") (pintype "power_in"))
      (node (ref "U7") (pin "M17") (pinfunction "MSEL0_M17") (pintype "input"))
      (node (ref "U7") (pin "N10") (pinfunction "GND_N10") (pintype "power_in"))
      (node (ref "U7") (pin "N11") (pinfunction "GND_N11") (pintype "power_in"))
      (node (ref "U7") (pin "N12") (pinfunction "GND_N12") (pintype "power_in"))
      (node (ref "U7") (pin "N13") (pinfunction "GND_N13") (pintype "power_in"))
      (node (ref "U7") (pin "N15") (pinfunction "GND_N15") (pintype "power_in"))
      (node (ref "U7") (pin "N3") (pinfunction "GND_N3") (pintype "power_in"))
      (node (ref "U7") (pin "P19") (pinfunction "GND_P19") (pintype "power_in"))
      (node (ref "U7") (pin "P8") (pinfunction "GND_P8") (pintype "power_in"))
      (node (ref "U7") (pin "R11") (pinfunction "GND_R11") (pintype "power_in"))
      (node (ref "U7") (pin "R13") (pinfunction "GND_R13") (pintype "power_in"))
      (node (ref "U7") (pin "R3") (pinfunction "GND_R3") (pintype "power_in"))
      (node (ref "U7") (pin "R9") (pinfunction "GND_R9") (pintype "power_in"))
      (node (ref "U7") (pin "T20") (pinfunction "GND_T20") (pintype "power_in"))
      (node (ref "U7") (pin "U3") (pinfunction "GND_U3") (pintype "power_in"))
      (node (ref "U7") (pin "U5") (pinfunction "GNDA1_U5") (pintype "power_in"))
      (node (ref "U7") (pin "V18") (pinfunction "GNDA4_V18") (pintype "power_in"))
      (node (ref "U7") (pin "V20") (pinfunction "GND_V20") (pintype "power_in"))
      (node (ref "U7") (pin "W3") (pinfunction "GND_W3") (pintype "power_in"))
      (node (ref "U7") (pin "Y11") (pinfunction "GND_Y11") (pintype "power_in"))
      (node (ref "U7") (pin "Y12") (pinfunction "GND_Y12") (pintype "power_in"))
      (node (ref "U7") (pin "Y15") (pinfunction "GND_Y15") (pintype "power_in"))
      (node (ref "U7") (pin "Y16") (pinfunction "GND_Y16") (pintype "power_in"))
      (node (ref "U7") (pin "Y18") (pinfunction "GND_Y18") (pintype "power_in"))
      (node (ref "U7") (pin "Y20") (pinfunction "GND_Y20") (pintype "power_in"))
      (node (ref "U7") (pin "Y5") (pinfunction "GND_Y5") (pintype "power_in"))
      (node (ref "U7") (pin "Y9") (pinfunction "GND_Y9") (pintype "power_in"))
      (node (ref "U8") (pin "2") (pinfunction "GND_2") (pintype "power_in"))
      (node (ref "U9") (pin "4") (pinfunction "GND_4") (pintype "power_in"))
    )
    (net (code "23") (name "LVDS_IO") (class "Default")
      (node (ref "C24") (pin "1") (pinfunction "0_1") (pintype "passive"))
      (node (ref "C25") (pin "1") (pinfunction "0_1") (pintype "passive"))
      (node (ref "D12") (pin "1") (pinfunction "L20_1") (pintype "passive"))
      (node (ref "R48") (pin "2") (pinfunction "2_2") (pintype "passive"))
      (node (ref "U7") (pin "E19") (pinfunction "VCCIO6_E19") (pintype "power_in"))
      (node (ref "U7") (pin "G19") (pinfunction "VCCIO6_G19") (pintype "power_in"))
      (node (ref "U7") (pin "J20") (pinfunction "VCCIO6_J20") (pintype "power_in"))
      (node (ref "U7") (pin "L19") (pinfunction "VCCIO6_L19") (pintype "power_in"))
    )
    (net (code "24") (name "Net-(D12-L21)") (class "Default")
      (node (ref "D12") (pin "2") (pinfunction "L21_2") (pintype "passive"))
      (node (ref "R58") (pin "1") (pinfunction "0_1") (pintype "passive"))
    )
    (net (code "25") (name "Net-(R46-0)") (class "Default")
      (node (ref "R46") (pin "1") (pinfunction "0_1") (pintype "passive"))
      (node (ref "U7") (pin "K6") (pinfunction "nSTATUS_K6") (pintype "bidirectional"))
    )
    (net (code "26") (name "Net-(R47-0)") (class "Default")
      (node (ref "R47") (pin "1") (pinfunction "0_1") (pintype "passive"))
      (node (ref "U7") (pin "K5") (pinfunction "nCONFIG_K5") (pintype "input"))
    )
    (net (code "27") (name "Net-(R54-0)") (class "Default")
      (node (ref "R54") (pin "1") (pinfunction "0_1") (pintype "passive"))
      (node (ref "U8") (pin "3") (pinfunction "OUT_3") (pintype "output"))
    )
    (net (code "28") (name "Net-(R56-0)") (class "Default")
      (node (ref "R56") (pin "1") (pinfunction "0_1") (pintype "passive"))
      (node (ref "U9") (pin "2") (pinfunction "DATA_2") (pintype "output"))
    )
    (net (code "29") (name "Net-(U7J-DCLK)") (class "Default")
      (node (ref "R49") (pin "2") (pinfunction "2_2") (pintype "passive"))
      (node (ref "U7") (pin "K2") (pinfunction "DCLK_K2") (pintype "bidirectional"))
    )
    (net (code "30") (name "Net-(U7J-nCE)") (class "Default")
      (node (ref "R50") (pin "2") (pinfunction "2_2") (pintype "passive"))
      (node (ref "U7") (pin "L3") (pinfunction "nCE_L3") (pintype "input"))
    )
    (net (code "31") (name "PLLA2V5") (class "Default")
      (node (ref "D10") (pin "2") (pinfunction "1_2") (pintype "passive"))
      (node (ref "D11") (pin "2") (pinfunction "1_2") (pintype "passive"))
      (node (ref "D8") (pin "2") (pinfunction "1_2") (pintype "passive"))
      (node (ref "D9") (pin "2") (pinfunction "1_2") (pintype "passive"))
      (node (ref "J6") (pin "4") (pinfunction "3_4") (pintype "passive"))
      (node (ref "J6") (pin "6") (pinfunction "5_6") (pintype "passive"))
      (node (ref "R52") (pin "2") (pinfunction "2_2") (pintype "passive"))
      (node (ref "R53") (pin "2") (pinfunction "2_2") (pintype "passive"))
      (node (ref "U7") (pin "F18") (pinfunction "VCCA2_F18") (pintype "power_in"))
      (node (ref "U7") (pin "G6") (pinfunction "VCCA3_G6") (pintype "power_in"))
      (node (ref "U7") (pin "L18") (pinfunction "MSEL1_L18") (pintype "input"))
      (node (ref "U7") (pin "T6") (pinfunction "VCCA1_T6") (pintype "power_in"))
      (node (ref "U7") (pin "U18") (pinfunction "VCCA4_U18") (pintype "power_in"))
    )
    (net (code "32") (name "PLLD1V2") (class "Default")
      (node (ref "U7") (pin "E17") (pinfunction "VCCD_PLL2_E17") (pintype "power_in"))
      (node (ref "U7") (pin "F6") (pinfunction "VCCD_PLL3_F6") (pintype "power_in"))
      (node (ref "U7") (pin "U6") (pinfunction "VCCD_PLL1_U6") (pintype "power_in"))
      (node (ref "U7") (pin "V17") (pinfunction "VCCD_PLL4_V17") (pintype "power_in"))
    )
    (net (code "33") (name "unconnected-(J6-Pad7)") (class "Default")
      (node (ref "J6") (pin "7") (pinfunction "7_7") (pintype "passive+no_connect"))
    )
    (net (code "34") (name "unconnected-(J6-Pad8)") (class "Default")
      (node (ref "J6") (pin "8") (pinfunction "8_8") (pintype "passive+no_connect"))
    )
    (net (code "35") (name "unconnected-(U8-OE-Pad1)") (class "Default")
      (node (ref "U8") (pin "1") (pinfunction "OE_1") (pintype "input+no_connect"))
    )
  )
)
